# power.net
KiCad netlist of a schematic drawn in Altium Designer
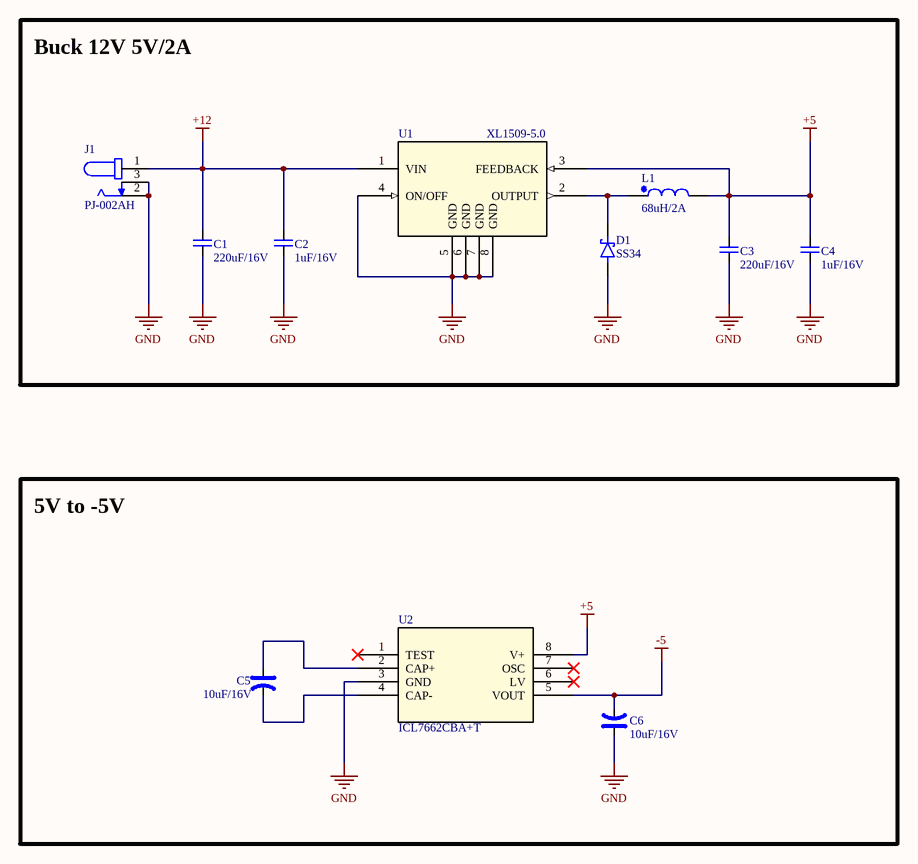
[diagram p0: power.SchDoc]

(export (version "E")
  (design (tool "Eeschema 10.0.6"))
  (components
    (comp (ref "C1")
      (value "220uF/16V")
      (footprint "CAP_C_1608X80")
      (description "CAP_Chip")
      (libsource (lib "Schlib") (part "CAP_SMD"))
    )
    (comp (ref "C2")
      (value "1uF/16V")
      (footprint "CAP_C_1608X80")
      (description "CAP_Chip")
      (libsource (lib "Schlib") (part "CAP_SMD"))
    )
    (comp (ref "C3")
      (value "220uF/16V")
      (footprint "CAP_C_1608X80")
      (description "CAP_Chip")
      (libsource (lib "Schlib") (part "CAP_SMD"))
    )
    (comp (ref "C4")
      (value "1uF/16V")
      (footprint "CAP_C_1608X80")
      (description "CAP_Chip")
      (libsource (lib "Schlib") (part "CAP_SMD"))
    )
    (comp (ref "C5")
      (value "10uF/16V")
      (footprint "CAP_MP_1608X90")
      (description "CAP_Polarization")
      (fields (field (name "PUBLISHER") "Altium Limited"))
      (libsource (lib "Schlib") (part "CAP_TH"))
    )
    (comp (ref "C6")
      (value "10uF/16V")
      (footprint "CAP_MP_1608X90")
      (description "CAP_Polarization")
      (fields (field (name "PUBLISHER") "Altium Limited"))
      (libsource (lib "Schlib") (part "CAP_TH"))
    )
    (comp (ref "D1")
      (value "SS34")
      (footprint "DIOM7959X265N")
      (description "Diode Schottky 40 V 3A Surface Mount SMC (DO-214AB)")
      (fields (field (name "MF") "onsemi"))
      (libsource (lib "Schlib") (part "SS34"))
    )
    (comp (ref "J1")
      (value "PJ-002AH")
      (footprint "CUI_PJ-002AH")
      (description "2.0 x 6.5 mm, 5.0 A, Horizontal, Through Hole, Dc Power Jack Connector")
      (fields (field (name "MF") "Same Sky"))
      (libsource (lib "Schlib") (part "PJ-002AH"))
    )
    (comp (ref "L1") (value "68uH/2A") (footprint "IND730660x480") (libsource (lib "Schlib") (part "_IND")))
    (comp (ref "U1")
      (value "XL1509-5.0")
      (footprint "SOP8SOIC-8_UMW")
      (description "Description")
      (fields (field (name "COPYRIGHT") "Copyright (C) 2025 Ultra Librarian. All rights reserved."))
      (libsource (lib "Schlib") (part "XL1509-5.0"))
    )
    (comp (ref "U2")
      (value "ICL7662CBA+T")
      (footprint "21-0041B_8_MXM")
      (description "CMOS Voltage Converters")
      (fields (field (name "COPYRIGHT") "Copyright (C) 2025 Ultra Librarian. All rights reserved."))
      (libsource (lib "Schlib") (part "ICL7662CBA+T"))
    )
  )
  (nets
    (net (code "1") (name "+5") (class "Default")
      (node (ref "C3") (pin "2") (pinfunction "2_2") (pintype "passive"))
      (node (ref "C4") (pin "2") (pinfunction "2_2") (pintype "passive"))
      (node (ref "L1") (pin "2") (pinfunction "2_2") (pintype "passive"))
      (node (ref "U1") (pin "3") (pinfunction "FEEDBACK_3") (pintype "input"))
      (node (ref "U2") (pin "8") (pinfunction "V+_8") (pintype "power_in"))
    )
    (net (code "2") (name "+12") (class "Default")
      (node (ref "C1") (pin "2") (pinfunction "2_2") (pintype "passive"))
      (node (ref "C2") (pin "2") (pinfunction "2_2") (pintype "passive"))
      (node (ref "J1") (pin "1") (pinfunction "1_1") (pintype "passive"))
      (node (ref "U1") (pin "1") (pinfunction "VIN_1") (pintype "power_in"))
    )
    (net (code "3") (name "-5") (class "Default")
      (node (ref "C6") (pin "2") (pinfunction "2_2") (pintype "passive"))
      (node (ref "U2") (pin "5") (pinfunction "VOUT_5") (pintype "passive"))
    )
    (net (code "4") (name "GND") (class "Default")
      (node (ref "C1") (pin "1") (pinfunction "1_1") (pintype "passive"))
      (node (ref "C2") (pin "1") (pinfunction "1_1") (pintype "passive"))
      (node (ref "C3") (pin "1") (pinfunction "1_1") (pintype "passive"))
      (node (ref "C4") (pin "1") (pinfunction "1_1") (pintype "passive"))
      (node (ref "C6") (pin "1") (pinfunction "1_1") (pintype "passive"))
      (node (ref "D1") (pin "A") (pinfunction "A_A") (pintype "passive"))
      (node (ref "J1") (pin "2") (pinfunction "2_2") (pintype "passive"))
      (node (ref "J1") (pin "3") (pinfunction "3_3") (pintype "passive"))
      (node (ref "U1") (pin "4") (pinfunction "ON/OFF_4") (pintype "input"))
      (node (ref "U1") (pin "5") (pinfunction "GND_5") (pintype "power_in"))
      (node (ref "U1") (pin "6") (pinfunction "GND_6") (pintype "power_in"))
      (node (ref "U1") (pin "7") (pinfunction "GND_7") (pintype "power_in"))
      (node (ref "U1") (pin "8") (pinfunction "GND_8") (pintype "power_in"))
      (node (ref "U2") (pin "3") (pinfunction "GND_3") (pintype "power_in"))
    )
    (net (code "5") (name "Net-(D1-K)") (class "Default")
      (node (ref "D1") (pin "C") (pinfunction "K_C") (pintype "passive"))
      (node (ref "L1") (pin "1") (pinfunction "1_1") (pintype "passive"))
      (node (ref "U1") (pin "2") (pinfunction "OUTPUT_2") (pintype "output"))
    )
    (net (code "6") (name "Net-(U2-CAP+)") (class "Default")
      (node (ref "C5") (pin "1") (pinfunction "1_1") (pintype "passive"))
      (node (ref "U2") (pin "2") (pinfunction "CAP+_2") (pintype "passive"))
    )
    (net (code "7") (name "Net-(U2-CAP-)") (class "Default")
      (node (ref "C5") (pin "2") (pinfunction "2_2") (pintype "passive"))
      (node (ref "U2") (pin "4") (pinfunction "CAP-_4") (pintype "passive"))
    )
    (net (code "8") (name "unconnected-(U2-LV-Pad6)") (class "Default")
      (node (ref "U2") (pin "6") (pinfunction "LV_6") (pintype "passive+no_connect"))
    )
    (net (code "9") (name "unconnected-(U2-OSC-Pad7)") (class "Default")
      (node (ref "U2") (pin "7") (pinfunction "OSC_7") (pintype "passive+no_connect"))
    )
    (net (code "10") (name "unconnected-(U2-TEST-Pad1)") (class "Default")
      (node (ref "U2") (pin "1") (pinfunction "TEST_1") (pintype "passive+no_connect"))
    )
  )
)
